# MBC3_1-3.net
KiCad netlist of a schematic drawn in EAGLE
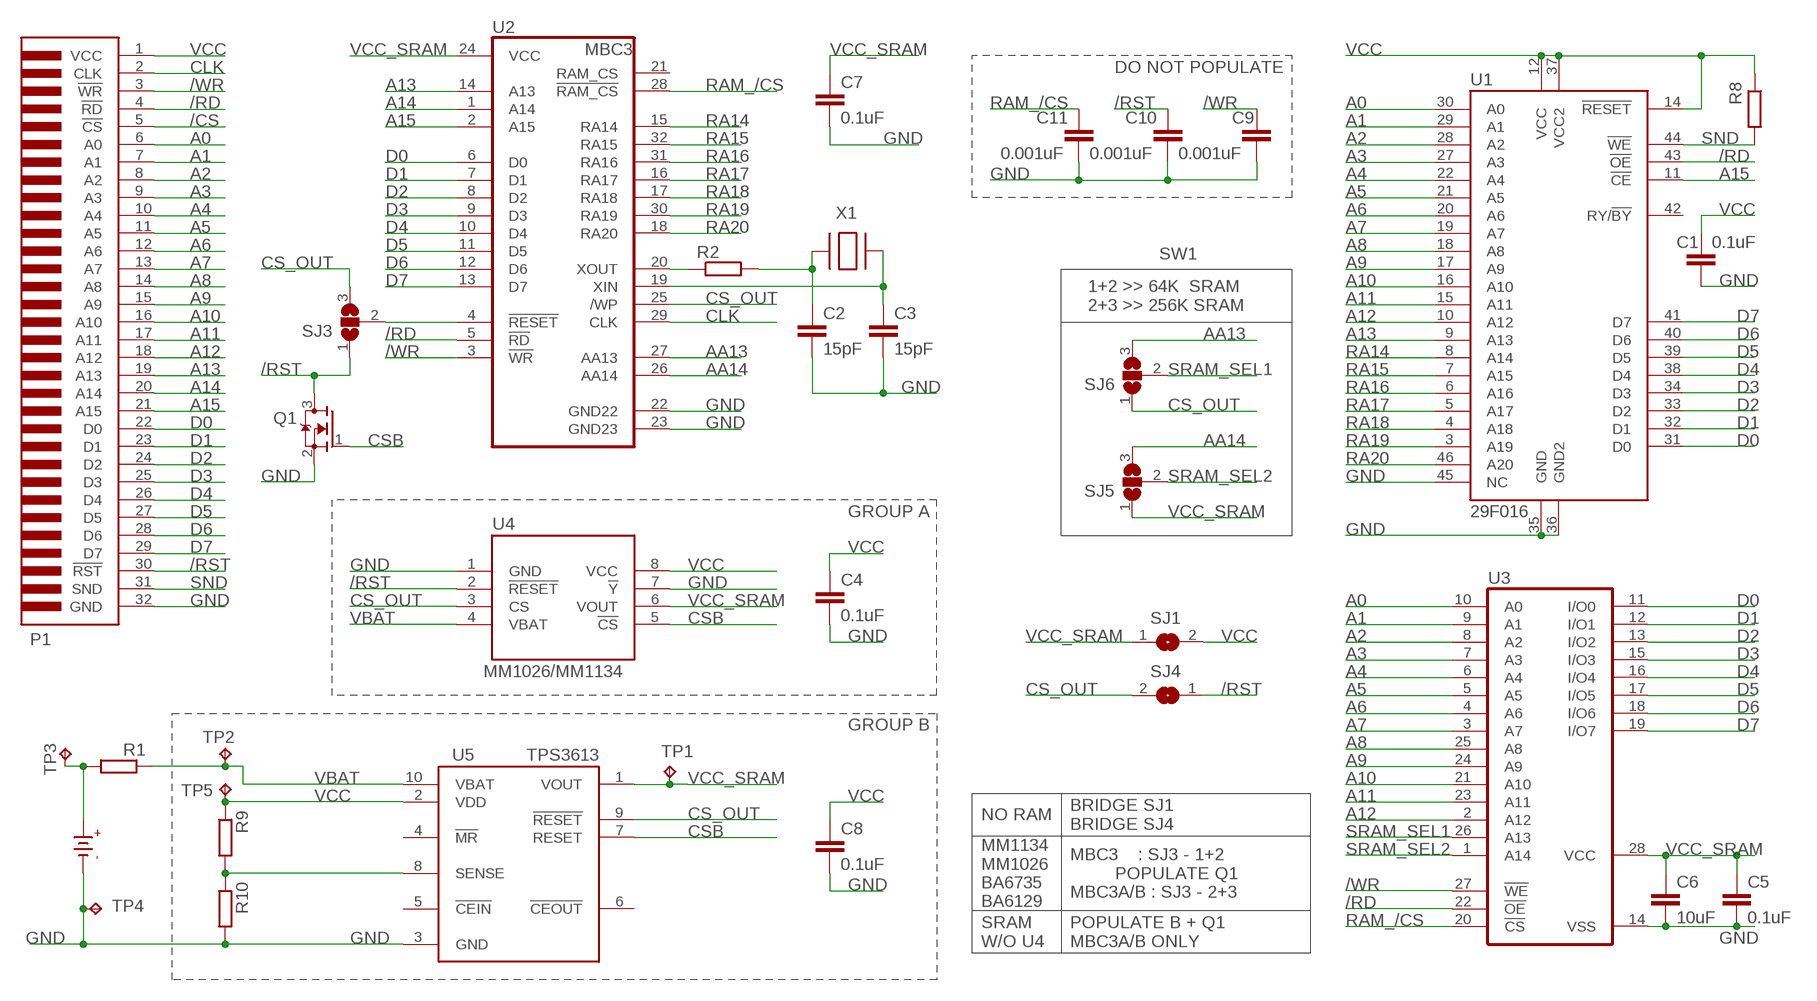
[diagram p0: schematic, sheet 1]

(export (version "E")
  (design (tool "Eeschema 10.0.6"))
  (components
    (comp (ref "B1")
      (value "CR2025")
      (footprint "eagle-import:CR2025")
      (libsource (lib "eagle-import") (part "CR2025"))
    )
    (comp (ref "C1")
      (value "0.1uF")
      (footprint "eagle-import:C0603")
      (libsource (lib "eagle-import") (part "C-EUC0603"))
    )
    (comp (ref "C2")
      (value "15pF")
      (footprint "eagle-import:C0603")
      (libsource (lib "eagle-import") (part "C-EUC0603"))
    )
    (comp (ref "C3")
      (value "15pF")
      (footprint "eagle-import:C0603")
      (libsource (lib "eagle-import") (part "C-EUC0603"))
    )
    (comp (ref "C4")
      (value "0.1uF")
      (footprint "eagle-import:C0603")
      (libsource (lib "eagle-import") (part "C-EUC0603"))
    )
    (comp (ref "C5")
      (value "0.1uF")
      (footprint "eagle-import:C0603")
      (libsource (lib "eagle-import") (part "C-EUC0603"))
    )
    (comp (ref "C6")
      (value "10uF")
      (footprint "eagle-import:C0603")
      (libsource (lib "eagle-import") (part "C-EUC0603"))
    )
    (comp (ref "C7")
      (value "0.1uF")
      (footprint "eagle-import:C0603")
      (libsource (lib "eagle-import") (part "C-EUC0603"))
    )
    (comp (ref "C8")
      (value "0.1uF")
      (footprint "eagle-import:C0603")
      (libsource (lib "eagle-import") (part "C-EUC0603"))
    )
    (comp (ref "C9")
      (value "0.001uF")
      (footprint "eagle-import:C0603")
      (libsource (lib "eagle-import") (part "C-EUC0603"))
    )
    (comp (ref "C10")
      (value "0.001uF")
      (footprint "eagle-import:C0603")
      (libsource (lib "eagle-import") (part "C-EUC0603"))
    )
    (comp (ref "C11")
      (value "0.001uF")
      (footprint "eagle-import:C0603")
      (libsource (lib "eagle-import") (part "C-EUC0603"))
    )
    (comp (ref "P1")
      (value "GBC_CART")
      (footprint "eagle-import:GBC_CART")
      (libsource (lib "eagle-import") (part "GBC_CART"))
    )
    (comp (ref "Q1")
      (value "2N7002")
      (footprint "eagle-import:SOT23")
      (libsource (lib "eagle-import") (part "MOSFET-NREFLOW"))
    )
    (comp (ref "R1")
      (value "RR0603")
      (footprint "eagle-import:R0603")
      (libsource (lib "eagle-import") (part "RR0603"))
    )
    (comp (ref "R2")
      (value "RR0603")
      (footprint "eagle-import:R0603")
      (libsource (lib "eagle-import") (part "RR0603"))
    )
    (comp (ref "R8")
      (value "RR0603")
      (footprint "eagle-import:R0603")
      (libsource (lib "eagle-import") (part "RR0603"))
    )
    (comp (ref "R9")
      (value "RR0603")
      (footprint "eagle-import:R0603")
      (libsource (lib "eagle-import") (part "RR0603"))
    )
    (comp (ref "R10")
      (value "RR0603")
      (footprint "eagle-import:R0603")
      (libsource (lib "eagle-import") (part "RR0603"))
    )
    (comp (ref "SJ1") (value "SJ") (footprint "eagle-import:SJ") (libsource (lib "eagle-import") (part "SJ")))
    (comp (ref "SJ3")
      (value "SJ2W")
      (footprint "eagle-import:SJ_2")
      (libsource (lib "eagle-import") (part "SJ2W"))
    )
    (comp (ref "SJ4") (value "SJ") (footprint "eagle-import:SJ") (libsource (lib "eagle-import") (part "SJ")))
    (comp (ref "SJ5")
      (value "SJ2W")
      (footprint "eagle-import:SJ_2")
      (libsource (lib "eagle-import") (part "SJ2W"))
    )
    (comp (ref "SJ6")
      (value "SJ2W")
      (footprint "eagle-import:SJ_2")
      (libsource (lib "eagle-import") (part "SJ2W"))
    )
    (comp (ref "TP1")
      (value "TPB1,27")
      (footprint "eagle-import:B1,27")
      (libsource (lib "eagle-import") (part "TPB1,27"))
    )
    (comp (ref "TP2")
      (value "TPB1,27")
      (footprint "eagle-import:B1,27")
      (libsource (lib "eagle-import") (part "TPB1,27"))
    )
    (comp (ref "TP3")
      (value "TPB1,27")
      (footprint "eagle-import:B1,27")
      (libsource (lib "eagle-import") (part "TPB1,27"))
    )
    (comp (ref "TP4")
      (value "TPB1,27")
      (footprint "eagle-import:B1,27")
      (libsource (lib "eagle-import") (part "TPB1,27"))
    )
    (comp (ref "TP5")
      (value "TPB1,27")
      (footprint "eagle-import:B1,27")
      (libsource (lib "eagle-import") (part "TPB1,27"))
    )
    (comp (ref "U1")
      (value "29F016")
      (footprint "eagle-import:TSOP-48")
      (libsource (lib "eagle-import") (part "29F016"))
    )
    (comp (ref "U2")
      (value "MBC3")
      (footprint "eagle-import:QFP-32")
      (libsource (lib "eagle-import") (part "MBC3"))
    )
    (comp (ref "U3")
      (value "62256_SRAM")
      (footprint "eagle-import:SOP-28L")
      (fields (field (name "MPN") "CY62256VNLL-70SNXI"))
      (libsource (lib "eagle-import") (part "62256_SRAM"))
    )
    (comp (ref "U4")
      (value "MM1134")
      (footprint "eagle-import:SOIC-8")
      (libsource (lib "eagle-import") (part "MM1134"))
    )
    (comp (ref "U5")
      (value "TPS3613")
      (footprint "eagle-import:MSOP-10")
      (libsource (lib "eagle-import") (part "TPS3613"))
    )
    (comp (ref "X1")
      (value "XTAL-3.2X1.5")
      (footprint "eagle-import:XTAL3215")
      (libsource (lib "eagle-import") (part "XTAL-3.2X1.5"))
    )
  )
  (nets
    (net (code "1") (name "/A0") (class "Default")
      (node (ref "P1") (pin "6") (pinfunction "A0_6") (pintype "output"))
      (node (ref "U1") (pin "30") (pinfunction "A0_30") (pintype "input"))
      (node (ref "U3") (pin "10") (pinfunction "A0_10") (pintype "input"))
    )
    (net (code "2") (name "/A1") (class "Default")
      (node (ref "P1") (pin "7") (pinfunction "A1_7") (pintype "output"))
      (node (ref "U1") (pin "29") (pinfunction "A1_29") (pintype "input"))
      (node (ref "U3") (pin "9") (pinfunction "A1_9") (pintype "input"))
    )
    (net (code "3") (name "/A2") (class "Default")
      (node (ref "P1") (pin "8") (pinfunction "A2_8") (pintype "output"))
      (node (ref "U1") (pin "28") (pinfunction "A2_28") (pintype "input"))
      (node (ref "U3") (pin "8") (pinfunction "A2_8") (pintype "input"))
    )
    (net (code "4") (name "/A3") (class "Default")
      (node (ref "P1") (pin "9") (pinfunction "A3_9") (pintype "output"))
      (node (ref "U1") (pin "27") (pinfunction "A3_27") (pintype "input"))
      (node (ref "U3") (pin "7") (pinfunction "A3_7") (pintype "input"))
    )
    (net (code "5") (name "/A4") (class "Default")
      (node (ref "P1") (pin "10") (pinfunction "A4_10") (pintype "output"))
      (node (ref "U1") (pin "22") (pinfunction "A4_22") (pintype "input"))
      (node (ref "U3") (pin "6") (pinfunction "A4_6") (pintype "input"))
    )
    (net (code "6") (name "/A5") (class "Default")
      (node (ref "P1") (pin "11") (pinfunction "A5_11") (pintype "output"))
      (node (ref "U1") (pin "21") (pinfunction "A5_21") (pintype "input"))
      (node (ref "U3") (pin "5") (pinfunction "A5_5") (pintype "input"))
    )
    (net (code "7") (name "/A6") (class "Default")
      (node (ref "P1") (pin "12") (pinfunction "A6_12") (pintype "output"))
      (node (ref "U1") (pin "20") (pinfunction "A6_20") (pintype "input"))
      (node (ref "U3") (pin "4") (pinfunction "A6_4") (pintype "input"))
    )
    (net (code "8") (name "/A7") (class "Default")
      (node (ref "P1") (pin "13") (pinfunction "A7_13") (pintype "output"))
      (node (ref "U1") (pin "19") (pinfunction "A7_19") (pintype "input"))
      (node (ref "U3") (pin "3") (pinfunction "A7_3") (pintype "input"))
    )
    (net (code "9") (name "/A8") (class "Default")
      (node (ref "P1") (pin "14") (pinfunction "A8_14") (pintype "output"))
      (node (ref "U1") (pin "18") (pinfunction "A8_18") (pintype "input"))
      (node (ref "U3") (pin "25") (pinfunction "A8_25") (pintype "input"))
    )
    (net (code "10") (name "/A9") (class "Default")
      (node (ref "P1") (pin "15") (pinfunction "A9_15") (pintype "output"))
      (node (ref "U1") (pin "17") (pinfunction "A9_17") (pintype "input"))
      (node (ref "U3") (pin "24") (pinfunction "A9_24") (pintype "input"))
    )
    (net (code "11") (name "/A10") (class "Default")
      (node (ref "P1") (pin "16") (pinfunction "A10_16") (pintype "output"))
      (node (ref "U1") (pin "16") (pinfunction "A10_16") (pintype "input"))
      (node (ref "U3") (pin "21") (pinfunction "A10_21") (pintype "input"))
    )
    (net (code "12") (name "/A11") (class "Default")
      (node (ref "P1") (pin "17") (pinfunction "A11_17") (pintype "output"))
      (node (ref "U1") (pin "15") (pinfunction "A11_15") (pintype "input"))
      (node (ref "U3") (pin "23") (pinfunction "A11_23") (pintype "input"))
    )
    (net (code "13") (name "/A12") (class "Default")
      (node (ref "P1") (pin "18") (pinfunction "A12_18") (pintype "output"))
      (node (ref "U1") (pin "10") (pinfunction "A12_10") (pintype "input"))
      (node (ref "U3") (pin "2") (pinfunction "A12_2") (pintype "input"))
    )
    (net (code "14") (name "/A13") (class "Default")
      (node (ref "P1") (pin "19") (pinfunction "A13_19") (pintype "output"))
      (node (ref "U1") (pin "9") (pinfunction "A13_9") (pintype "input"))
      (node (ref "U2") (pin "14") (pinfunction "A13_14") (pintype "input"))
    )
    (net (code "15") (name "/A14") (class "Default")
      (node (ref "P1") (pin "20") (pinfunction "A14_20") (pintype "output"))
      (node (ref "U2") (pin "1") (pinfunction "A14_1") (pintype "input"))
    )
    (net (code "16") (name "/A15") (class "Default")
      (node (ref "P1") (pin "21") (pinfunction "A15_21") (pintype "output"))
      (node (ref "U1") (pin "11") (pinfunction "~{CE}_11") (pintype "input"))
      (node (ref "U2") (pin "2") (pinfunction "A15_2") (pintype "input"))
    )
    (net (code "17") (name "/AA13") (class "Default")
      (node (ref "SJ6") (pin "3") (pinfunction "3_3") (pintype "passive"))
      (node (ref "U2") (pin "27") (pinfunction "AA13_27") (pintype "output"))
    )
    (net (code "18") (name "/AA14") (class "Default")
      (node (ref "SJ5") (pin "3") (pinfunction "3_3") (pintype "passive"))
      (node (ref "U2") (pin "26") (pinfunction "AA14_26") (pintype "output"))
    )
    (net (code "19") (name "/CLK") (class "Default")
      (node (ref "P1") (pin "2") (pinfunction "CLK_2") (pintype "output"))
      (node (ref "U2") (pin "29") (pinfunction "CLK_29") (pintype "output"))
    )
    (net (code "20") (name "/CSB") (class "Default")
      (node (ref "Q1") (pin "1") (pinfunction "G_1") (pintype "bidirectional"))
      (node (ref "U4") (pin "5") (pinfunction "~{CS}_5") (pintype "output"))
      (node (ref "U5") (pin "7") (pinfunction "RESET_7") (pintype "output"))
    )
    (net (code "21") (name "/CS_OUT") (class "Default")
      (node (ref "SJ3") (pin "3") (pinfunction "3_3") (pintype "passive"))
      (node (ref "SJ4") (pin "2") (pinfunction "2_2") (pintype "passive"))
      (node (ref "SJ6") (pin "1") (pinfunction "1_1") (pintype "passive"))
      (node (ref "U2") (pin "25") (pinfunction "/WP_25") (pintype "output"))
      (node (ref "U4") (pin "3") (pinfunction "CS_3") (pintype "output"))
      (node (ref "U5") (pin "9") (pinfunction "~{RESET}_9") (pintype "output"))
    )
    (net (code "22") (name "/D0") (class "Default")
      (node (ref "P1") (pin "22") (pinfunction "D0_22") (pintype "bidirectional"))
      (node (ref "U1") (pin "31") (pinfunction "D0_31") (pintype "bidirectional"))
      (node (ref "U2") (pin "6") (pinfunction "D0_6") (pintype "input"))
      (node (ref "U3") (pin "11") (pinfunction "I/O0_11") (pintype "bidirectional"))
    )
    (net (code "23") (name "/D1") (class "Default")
      (node (ref "P1") (pin "23") (pinfunction "D1_23") (pintype "bidirectional"))
      (node (ref "U1") (pin "32") (pinfunction "D1_32") (pintype "bidirectional"))
      (node (ref "U2") (pin "7") (pinfunction "D1_7") (pintype "input"))
      (node (ref "U3") (pin "12") (pinfunction "I/O1_12") (pintype "bidirectional"))
    )
    (net (code "24") (name "/D2") (class "Default")
      (node (ref "P1") (pin "24") (pinfunction "D2_24") (pintype "bidirectional"))
      (node (ref "U1") (pin "33") (pinfunction "D2_33") (pintype "bidirectional"))
      (node (ref "U2") (pin "8") (pinfunction "D2_8") (pintype "input"))
      (node (ref "U3") (pin "13") (pinfunction "I/O2_13") (pintype "bidirectional"))
    )
    (net (code "25") (name "/D3") (class "Default")
      (node (ref "P1") (pin "25") (pinfunction "D3_25") (pintype "bidirectional"))
      (node (ref "U1") (pin "34") (pinfunction "D3_34") (pintype "bidirectional"))
      (node (ref "U2") (pin "9") (pinfunction "D3_9") (pintype "input"))
      (node (ref "U3") (pin "15") (pinfunction "I/O3_15") (pintype "bidirectional"))
    )
    (net (code "26") (name "/D4") (class "Default")
      (node (ref "P1") (pin "26") (pinfunction "D4_26") (pintype "bidirectional"))
      (node (ref "U1") (pin "38") (pinfunction "D4_38") (pintype "bidirectional"))
      (node (ref "U2") (pin "10") (pinfunction "D4_10") (pintype "input"))
      (node (ref "U3") (pin "16") (pinfunction "I/O4_16") (pintype "bidirectional"))
    )
    (net (code "27") (name "/D5") (class "Default")
      (node (ref "P1") (pin "27") (pinfunction "D5_27") (pintype "bidirectional"))
      (node (ref "U1") (pin "39") (pinfunction "D5_39") (pintype "bidirectional"))
      (node (ref "U2") (pin "11") (pinfunction "D5_11") (pintype "input"))
      (node (ref "U3") (pin "17") (pinfunction "I/O5_17") (pintype "bidirectional"))
    )
    (net (code "28") (name "/D6") (class "Default")
      (node (ref "P1") (pin "28") (pinfunction "D6_28") (pintype "bidirectional"))
      (node (ref "U1") (pin "40") (pinfunction "D6_40") (pintype "bidirectional"))
      (node (ref "U2") (pin "12") (pinfunction "D6_12") (pintype "input"))
      (node (ref "U3") (pin "18") (pinfunction "I/O6_18") (pintype "bidirectional"))
    )
    (net (code "29") (name "/D7") (class "Default")
      (node (ref "P1") (pin "29") (pinfunction "D7_29") (pintype "bidirectional"))
      (node (ref "U1") (pin "41") (pinfunction "D7_41") (pintype "bidirectional"))
      (node (ref "U2") (pin "13") (pinfunction "D7_13") (pintype "input"))
      (node (ref "U3") (pin "19") (pinfunction "I/O7_19") (pintype "bidirectional"))
    )
    (net (code "30") (name "/GND") (class "Default")
      (node (ref "B1") (pin "-") (pinfunction "-_-") (pintype "power_in"))
      (node (ref "C1") (pin "2") (pinfunction "2_2") (pintype "passive"))
      (node (ref "C10") (pin "2") (pinfunction "2_2") (pintype "passive"))
      (node (ref "C11") (pin "2") (pinfunction "2_2") (pintype "passive"))
      (node (ref "C2") (pin "2") (pinfunction "2_2") (pintype "passive"))
      (node (ref "C3") (pin "2") (pinfunction "2_2") (pintype "passive"))
      (node (ref "C4") (pin "2") (pinfunction "2_2") (pintype "passive"))
      (node (ref "C5") (pin "2") (pinfunction "2_2") (pintype "passive"))
      (node (ref "C6") (pin "2") (pinfunction "2_2") (pintype "passive"))
      (node (ref "C7") (pin "2") (pinfunction "2_2") (pintype "passive"))
      (node (ref "C8") (pin "2") (pinfunction "2_2") (pintype "passive"))
      (node (ref "C9") (pin "2") (pinfunction "2_2") (pintype "passive"))
      (node (ref "P1") (pin "32") (pinfunction "GND_32") (pintype "power_in"))
      (node (ref "Q1") (pin "2") (pinfunction "S_2") (pintype "bidirectional"))
      (node (ref "R10") (pin "2") (pinfunction "2_2") (pintype "passive"))
      (node (ref "TP4") (pin "TP") (pinfunction "TP_TP") (pintype "input"))
      (node (ref "U1") (pin "35") (pinfunction "GND_35") (pintype "power_in"))
      (node (ref "U1") (pin "36") (pinfunction "GND2_36") (pintype "power_in"))
      (node (ref "U1") (pin "45") (pinfunction "NC_45") (pintype "input"))
      (node (ref "U2") (pin "22") (pinfunction "GND22_22") (pintype "power_in"))
      (node (ref "U2") (pin "23") (pinfunction "GND23_23") (pintype "power_in"))
      (node (ref "U3") (pin "14") (pinfunction "VSS_14") (pintype "power_in"))
      (node (ref "U4") (pin "1") (pinfunction "GND_1") (pintype "power_in"))
      (node (ref "U4") (pin "7") (pinfunction "~{Y}_7") (pintype "input"))
      (node (ref "U5") (pin "3") (pinfunction "GND_3") (pintype "power_in"))
    )
    (net (code "31") (name "/RA14") (class "Default")
      (node (ref "U1") (pin "8") (pinfunction "A14_8") (pintype "input"))
      (node (ref "U2") (pin "15") (pinfunction "RA14_15") (pintype "output"))
    )
    (net (code "32") (name "/RA15") (class "Default")
      (node (ref "U1") (pin "7") (pinfunction "A15_7") (pintype "input"))
      (node (ref "U2") (pin "32") (pinfunction "RA15_32") (pintype "output"))
    )
    (net (code "33") (name "/RA16") (class "Default")
      (node (ref "U1") (pin "6") (pinfunction "A16_6") (pintype "input"))
      (node (ref "U2") (pin "31") (pinfunction "RA16_31") (pintype "output"))
    )
    (net (code "34") (name "/RA17") (class "Default")
      (node (ref "U1") (pin "5") (pinfunction "A17_5") (pintype "input"))
      (node (ref "U2") (pin "16") (pinfunction "RA17_16") (pintype "output"))
    )
    (net (code "35") (name "/RA18") (class "Default")
      (node (ref "U1") (pin "4") (pinfunction "A18_4") (pintype "input"))
      (node (ref "U2") (pin "17") (pinfunction "RA18_17") (pintype "output"))
    )
    (net (code "36") (name "/RA19") (class "Default")
      (node (ref "U1") (pin "3") (pinfunction "A19_3") (pintype "input"))
      (node (ref "U2") (pin "30") (pinfunction "RA19_30") (pintype "output"))
    )
    (net (code "37") (name "/RA20") (class "Default")
      (node (ref "U1") (pin "46") (pinfunction "A20_46") (pintype "input"))
      (node (ref "U2") (pin "18") (pinfunction "RA20_18") (pintype "output"))
    )
    (net (code "38") (name "/RAM_{slash}CS") (class "Default")
      (node (ref "C11") (pin "1") (pinfunction "1_1") (pintype "passive"))
      (node (ref "U2") (pin "28") (pinfunction "~{RAM_CS}_28") (pintype "output"))
      (node (ref "U3") (pin "20") (pinfunction "~{CS}_20") (pintype "input"))
    )
    (net (code "39") (name "/SND") (class "Default")
      (node (ref "P1") (pin "31") (pinfunction "SND_31") (pintype "bidirectional"))
      (node (ref "R8") (pin "2") (pinfunction "2_2") (pintype "passive"))
      (node (ref "U1") (pin "44") (pinfunction "~{WE}_44") (pintype "input"))
    )
    (net (code "40") (name "/SRAM_SEL1") (class "Default")
      (node (ref "SJ6") (pin "2") (pinfunction "2_2") (pintype "passive"))
      (node (ref "U3") (pin "26") (pinfunction "A13_26") (pintype "input"))
    )
    (net (code "41") (name "/SRAM_SEL2") (class "Default")
      (node (ref "SJ5") (pin "2") (pinfunction "2_2") (pintype "passive"))
      (node (ref "U3") (pin "1") (pinfunction "A14_1") (pintype "input"))
    )
    (net (code "42") (name "/VBAT") (class "Default")
      (node (ref "R1") (pin "1") (pinfunction "1_1") (pintype "passive"))
      (node (ref "TP2") (pin "TP") (pinfunction "TP_TP") (pintype "input"))
      (node (ref "U4") (pin "4") (pinfunction "VBAT_4") (pintype "power_in"))
      (node (ref "U5") (pin "10") (pinfunction "VBAT_10") (pintype "power_in"))
    )
    (net (code "43") (name "/VCC") (class "Default")
      (node (ref "C1") (pin "1") (pinfunction "1_1") (pintype "passive"))
      (node (ref "C4") (pin "1") (pinfunction "1_1") (pintype "passive"))
      (node (ref "C8") (pin "1") (pinfunction "1_1") (pintype "passive"))
      (node (ref "P1") (pin "1") (pinfunction "VCC_1") (pintype "power_in"))
      (node (ref "R8") (pin "1") (pinfunction "1_1") (pintype "passive"))
      (node (ref "R9") (pin "1") (pinfunction "1_1") (pintype "passive"))
      (node (ref "SJ1") (pin "2") (pinfunction "2_2") (pintype "passive"))
      (node (ref "TP5") (pin "TP") (pinfunction "TP_TP") (pintype "input"))
      (node (ref "U1") (pin "12") (pinfunction "VCC_12") (pintype "power_in"))
      (node (ref "U1") (pin "14") (pinfunction "~{RESET}_14") (pintype "input"))
      (node (ref "U1") (pin "37") (pinfunction "VCC2_37") (pintype "power_in"))
      (node (ref "U4") (pin "8") (pinfunction "VCC_8") (pintype "power_in"))
      (node (ref "U5") (pin "2") (pinfunction "VDD_2") (pintype "power_in"))
    )
    (net (code "44") (name "/VCC_SRAM") (class "Default")
      (node (ref "C5") (pin "1") (pinfunction "1_1") (pintype "passive"))
      (node (ref "C6") (pin "1") (pinfunction "1_1") (pintype "passive"))
      (node (ref "C7") (pin "1") (pinfunction "1_1") (pintype "passive"))
      (node (ref "SJ1") (pin "1") (pinfunction "1_1") (pintype "passive"))
      (node (ref "SJ5") (pin "1") (pinfunction "1_1") (pintype "passive"))
      (node (ref "TP1") (pin "TP") (pinfunction "TP_TP") (pintype "input"))
      (node (ref "U2") (pin "24") (pinfunction "VCC_24") (pintype "power_in"))
      (node (ref "U3") (pin "28") (pinfunction "VCC_28") (pintype "power_in"))
      (node (ref "U4") (pin "6") (pinfunction "VOUT_6") (pintype "power_in"))
      (node (ref "U5") (pin "1") (pinfunction "VOUT_1") (pintype "power_in"))
    )
    (net (code "45") (name "/{slash}CS") (class "Default")
      (node (ref "P1") (pin "5") (pinfunction "~{CS}_5") (pintype "output"))
    )
    (net (code "46") (name "/{slash}RD") (class "Default")
      (node (ref "P1") (pin "4") (pinfunction "~{RD}_4") (pintype "output"))
      (node (ref "U1") (pin "43") (pinfunction "~{OE}_43") (pintype "input"))
      (node (ref "U2") (pin "5") (pinfunction "~{RD}_5") (pintype "input"))
      (node (ref "U3") (pin "22") (pinfunction "~{OE}_22") (pintype "input"))
    )
    (net (code "47") (name "/{slash}RST") (class "Default")
      (node (ref "C10") (pin "1") (pinfunction "1_1") (pintype "passive"))
      (node (ref "P1") (pin "30") (pinfunction "~{RST}_30") (pintype "bidirectional"))
      (node (ref "Q1") (pin "3") (pinfunction "D_3") (pintype "bidirectional"))
      (node (ref "SJ3") (pin "1") (pinfunction "1_1") (pintype "passive"))
      (node (ref "SJ4") (pin "1") (pinfunction "1_1") (pintype "passive"))
      (node (ref "U4") (pin "2") (pinfunction "~{RESET}_2") (pintype "input"))
    )
    (net (code "48") (name "/{slash}WR") (class "Default")
      (node (ref "C9") (pin "1") (pinfunction "1_1") (pintype "passive"))
      (node (ref "P1") (pin "3") (pinfunction "~{WR}_3") (pintype "output"))
      (node (ref "U2") (pin "3") (pinfunction "~{WR}_3") (pintype "input"))
      (node (ref "U3") (pin "27") (pinfunction "~{WE}_27") (pintype "input"))
    )
    (net (code "49") (name "Net-(B1-Pad+)") (class "Default")
      (node (ref "B1") (pin "+") (pinfunction "+_+") (pintype "power_in"))
      (node (ref "R1") (pin "2") (pinfunction "2_2") (pintype "passive"))
      (node (ref "TP3") (pin "TP") (pinfunction "TP_TP") (pintype "input"))
    )
    (net (code "50") (name "Net-(C2-Pad1)") (class "Default")
      (node (ref "C2") (pin "1") (pinfunction "1_1") (pintype "passive"))
      (node (ref "R2") (pin "2") (pinfunction "2_2") (pintype "passive"))
      (node (ref "X1") (pin "P$2") (pinfunction "P$2_P$2") (pintype "bidirectional"))
    )
    (net (code "51") (name "Net-(U2-XIN)") (class "Default")
      (node (ref "C3") (pin "1") (pinfunction "1_1") (pintype "passive"))
      (node (ref "U2") (pin "19") (pinfunction "XIN_19") (pintype "input"))
      (node (ref "X1") (pin "P$1") (pinfunction "P$1_P$1") (pintype "bidirectional"))
    )
    (net (code "52") (name "Net-(U2-XOUT)") (class "Default")
      (node (ref "R2") (pin "1") (pinfunction "1_1") (pintype "passive"))
      (node (ref "U2") (pin "20") (pinfunction "XOUT_20") (pintype "output"))
    )
    (net (code "53") (name "Net-(U2-~{RESET})") (class "Default")
      (node (ref "SJ3") (pin "2") (pinfunction "2_2") (pintype "passive"))
      (node (ref "U2") (pin "4") (pinfunction "~{RESET}_4") (pintype "input"))
    )
    (net (code "54") (name "Net-(U5-SENSE)") (class "Default")
      (node (ref "R10") (pin "1") (pinfunction "1_1") (pintype "passive"))
      (node (ref "R9") (pin "2") (pinfunction "2_2") (pintype "passive"))
      (node (ref "U5") (pin "8") (pinfunction "SENSE_8") (pintype "input"))
    )
    (net (code "55") (name "unconnected-(U1-RY{slash}~{BY}-Pad42)") (class "Default")
      (node (ref "U1") (pin "42") (pinfunction "RY/~{BY}_42") (pintype "output"))
    )
    (net (code "56") (name "unconnected-(U2-RAM_CS-Pad21)") (class "Default")
      (node (ref "U2") (pin "21") (pinfunction "RAM_CS_21") (pintype "output"))
    )
    (net (code "57") (name "unconnected-(U5-~{CEIN}-Pad5)") (class "Default")
      (node (ref "U5") (pin "5") (pinfunction "~{CEIN}_5") (pintype "input"))
    )
    (net (code "58") (name "unconnected-(U5-~{CEOUT}-Pad6)") (class "Default")
      (node (ref "U5") (pin "6") (pinfunction "~{CEOUT}_6") (pintype "output"))
    )
    (net (code "59") (name "unconnected-(U5-~{MR}-Pad4)") (class "Default")
      (node (ref "U5") (pin "4") (pinfunction "~{MR}_4") (pintype "input"))
    )
  )
)
